# sch.net
KiCad netlist of a schematic drawn in Altium Designer
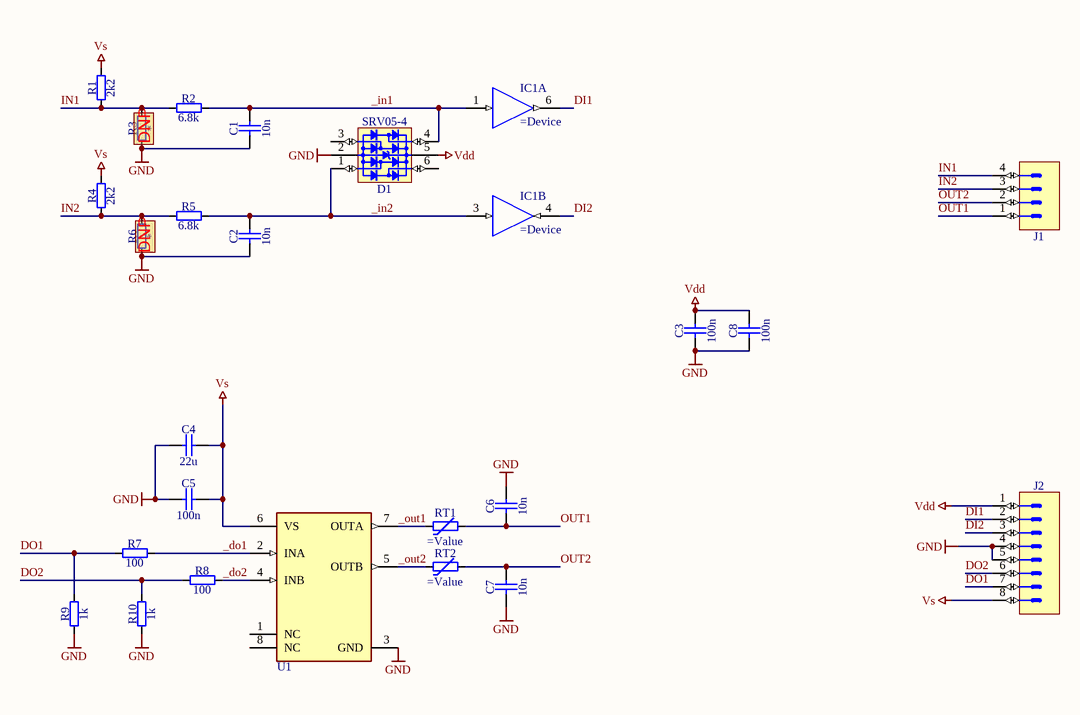
[diagram p0: sch.SchDoc]

(export (version "E")
  (design (tool "Eeschema 10.0.6"))
  (components
    (comp (ref "C1")
      (value "10n")
      (footprint "Capacitors SMD:CAPC1608X85N")
      (description "Non-polarised capacitor")
      (libsource (lib "mopedka ver") (part "Capacitor - non polarized"))
    )
    (comp (ref "C2")
      (value "10n")
      (footprint "Capacitors SMD:CAPC1608X85N")
      (description "Non-polarised capacitor")
      (libsource (lib "mopedka ver") (part "Capacitor - non polarized"))
    )
    (comp (ref "C3")
      (value "100n")
      (footprint "Capacitors SMD:CAPC1608X85N")
      (description "Non-polarised capacitor")
      (libsource (lib "mopedka ver") (part "Capacitor - non polarized"))
    )
    (comp (ref "C4")
      (value "22u")
      (footprint "Capacitors SMD:CAPC3216X140N")
      (description "Non-polarised capacitor")
      (libsource (lib "mopedka ver") (part "Capacitor - non polarized"))
    )
    (comp (ref "C5")
      (value "100n")
      (footprint "Capacitors SMD:CAPC1608X85N")
      (description "Non-polarised capacitor")
      (libsource (lib "mopedka ver") (part "Capacitor - non polarized"))
    )
    (comp (ref "C6")
      (value "10n")
      (footprint "Capacitors SMD:CAPC1608X85N")
      (description "Non-polarised capacitor")
      (libsource (lib "mopedka ver") (part "Capacitor - non polarized"))
    )
    (comp (ref "C7")
      (value "10n")
      (footprint "Capacitors SMD:CAPC1608X85N")
      (description "Non-polarised capacitor")
      (libsource (lib "mopedka ver") (part "Capacitor - non polarized"))
    )
    (comp (ref "C8")
      (value "100n")
      (footprint "Capacitors SMD:CAPC1608X85N")
      (description "Non-polarised capacitor")
      (libsource (lib "mopedka ver") (part "Capacitor - non polarized"))
    )
    (comp (ref "D1")
      (value "SRV05-4")
      (footprint "ICs And Semiconductors SMD:SOT95P280X110-6N")
      (description "RailClamps Low Capacitance TVS Diode Array")
      (libsource (lib "mopedka ver") (part "SRV05-4"))
    )
    (comp (ref "IC1")
      (value "~")
      (footprint "ICs And Semiconductors SMD:SOT65P220X110-6N")
      (description "Dual Schmitt-Trigger Buffer")
      (libsource (lib "mopedka ver") (part "742G17"))
    )
    (comp (ref "J1")
      (value "~")
      (footprint "Connectors THD:MOLEX_22-27-2041")
      (description "Connector 4 Male")
      (libsource (lib "Connectors") (part "Connector 4 Male"))
    )
    (comp (ref "J2")
      (value "~")
      (footprint "MOLEX THD:MOLEX_22-27-2081")
      (description "Connector 8 Male")
      (libsource (lib "Connectors") (part "Connector 8 Male"))
    )
    (comp (ref "R1")
      (value "2k2")
      (footprint "Resistors SMD:RESC3116X65N")
      (description "Resistor")
      (libsource (lib "mopedka ver") (part "Resistor"))
    )
    (comp (ref "R2")
      (value "6.8k")
      (footprint "Resistors SMD:RESC3116X65N")
      (description "Resistor")
      (libsource (lib "mopedka ver") (part "Resistor"))
    )
    (comp (ref "R3")
      (value "*")
      (footprint "Resistors SMD:RESC1608X55N")
      (description "Resistor")
      (libsource (lib "mopedka ver") (part "Resistor"))
    )
    (comp (ref "R4")
      (value "2k2")
      (footprint "Resistors SMD:RESC3116X65N")
      (description "Resistor")
      (libsource (lib "mopedka ver") (part "Resistor"))
    )
    (comp (ref "R5")
      (value "6.8k")
      (footprint "Resistors SMD:RESC3116X65N")
      (description "Resistor")
      (libsource (lib "mopedka ver") (part "Resistor"))
    )
    (comp (ref "R6")
      (value "*")
      (footprint "Resistors SMD:RESC1608X55N")
      (description "Resistor")
      (libsource (lib "mopedka ver") (part "Resistor"))
    )
    (comp (ref "R7")
      (value "100")
      (footprint "Resistors SMD:RESC1608X55N")
      (description "Resistor")
      (libsource (lib "Resistors") (part "Resistor"))
    )
    (comp (ref "R8")
      (value "100")
      (footprint "Resistors SMD:RESC1608X55N")
      (description "Resistor")
      (libsource (lib "Resistors") (part "Resistor"))
    )
    (comp (ref "R9")
      (value "1k")
      (footprint "Resistors SMD:RESC1608X55N")
      (description "Resistor")
      (libsource (lib "Resistors") (part "Resistor"))
    )
    (comp (ref "R10")
      (value "1k")
      (footprint "Resistors SMD:RESC1608X55N")
      (description "Resistor")
      (libsource (lib "Resistors") (part "Resistor"))
    )
    (comp (ref "RT1")
      (value "~")
      (footprint "Fuses:FUSC_LITTELFUSE_466")
      (description "Thermistor NTC (Positive Temperature Coefficient)")
      (libsource (lib "Resistors") (part "Thermistor PTC"))
    )
    (comp (ref "RT2")
      (value "~")
      (footprint "Fuses:FUSC_LITTELFUSE_466")
      (description "Thermistor NTC (Positive Temperature Coefficient)")
      (libsource (lib "Resistors") (part "Thermistor PTC"))
    )
    (comp (ref "U1")
      (value "IR4427STRPBF")
      (footprint "ICs And Semiconductors SMD:SOIC127P600X175-8N")
      (libsource (lib "IC_Infineon_IR4427STRPBF_eec") (part "IR4427STRPBF"))
    )
  )
  (nets
    (net (code "1") (name "/DI1") (class "Default")
      (node (ref "IC1") (pin "6") (pinfunction "OUT_6") (pintype "output"))
      (node (ref "J2") (pin "2") (pinfunction "2_2") (pintype "bidirectional"))
    )
    (net (code "2") (name "/DI2") (class "Default")
      (node (ref "IC1") (pin "4") (pinfunction "OUT_4") (pintype "input"))
      (node (ref "J2") (pin "3") (pinfunction "3_3") (pintype "bidirectional"))
    )
    (net (code "3") (name "/DO1") (class "Default")
      (node (ref "J2") (pin "7") (pinfunction "7_7") (pintype "bidirectional"))
      (node (ref "R7") (pin "1") (pinfunction "1_1") (pintype "passive"))
      (node (ref "R9") (pin "2") (pinfunction "2_2") (pintype "passive"))
    )
    (net (code "4") (name "/DO2") (class "Default")
      (node (ref "J2") (pin "6") (pinfunction "6_6") (pintype "bidirectional"))
      (node (ref "R10") (pin "2") (pinfunction "2_2") (pintype "passive"))
      (node (ref "R8") (pin "1") (pinfunction "1_1") (pintype "passive"))
    )
    (net (code "5") (name "/IN1") (class "Default")
      (node (ref "J1") (pin "4") (pinfunction "4_4") (pintype "bidirectional"))
      (node (ref "R1") (pin "1") (pinfunction "1_1") (pintype "passive"))
      (node (ref "R2") (pin "1") (pinfunction "1_1") (pintype "passive"))
      (node (ref "R3") (pin "2") (pinfunction "2_2") (pintype "passive"))
    )
    (net (code "6") (name "/IN2") (class "Default")
      (node (ref "J1") (pin "3") (pinfunction "3_3") (pintype "bidirectional"))
      (node (ref "R4") (pin "1") (pinfunction "1_1") (pintype "passive"))
      (node (ref "R5") (pin "1") (pinfunction "1_1") (pintype "passive"))
      (node (ref "R6") (pin "2") (pinfunction "2_2") (pintype "passive"))
    )
    (net (code "7") (name "/OUT1") (class "Default")
      (node (ref "C6") (pin "1") (pinfunction "1_1") (pintype "passive"))
      (node (ref "J1") (pin "1") (pinfunction "1_1") (pintype "bidirectional"))
      (node (ref "RT1") (pin "2") (pinfunction "2_2") (pintype "passive"))
    )
    (net (code "8") (name "/OUT2") (class "Default")
      (node (ref "C7") (pin "2") (pinfunction "2_2") (pintype "passive"))
      (node (ref "J1") (pin "2") (pinfunction "2_2") (pintype "bidirectional"))
      (node (ref "RT2") (pin "2") (pinfunction "2_2") (pintype "passive"))
    )
    (net (code "9") (name "/_do1") (class "Default")
      (node (ref "R7") (pin "2") (pinfunction "2_2") (pintype "passive"))
      (node (ref "U1") (pin "2") (pinfunction "INA_2") (pintype "input"))
    )
    (net (code "10") (name "/_do2") (class "Default")
      (node (ref "R8") (pin "2") (pinfunction "2_2") (pintype "passive"))
      (node (ref "U1") (pin "4") (pinfunction "INB_4") (pintype "input"))
    )
    (net (code "11") (name "/_in1") (class "Default")
      (node (ref "C1") (pin "2") (pinfunction "2_2") (pintype "passive"))
      (node (ref "D1") (pin "4") (pinfunction "I/O3_4") (pintype "bidirectional"))
      (node (ref "IC1") (pin "1") (pinfunction "IN_1") (pintype "input"))
      (node (ref "R2") (pin "2") (pinfunction "2_2") (pintype "passive"))
    )
    (net (code "12") (name "/_in2") (class "Default")
      (node (ref "C2") (pin "2") (pinfunction "2_2") (pintype "passive"))
      (node (ref "D1") (pin "1") (pinfunction "I/O1_1") (pintype "bidirectional"))
      (node (ref "IC1") (pin "3") (pinfunction "IN_3") (pintype "input"))
      (node (ref "R5") (pin "2") (pinfunction "2_2") (pintype "passive"))
    )
    (net (code "13") (name "/_out1") (class "Default")
      (node (ref "RT1") (pin "1") (pinfunction "1_1") (pintype "passive"))
      (node (ref "U1") (pin "7") (pinfunction "OUTA_7") (pintype "output"))
    )
    (net (code "14") (name "/_out2") (class "Default")
      (node (ref "RT2") (pin "1") (pinfunction "1_1") (pintype "passive"))
      (node (ref "U1") (pin "5") (pinfunction "OUTB_5") (pintype "output"))
    )
    (net (code "15") (name "GND") (class "Default")
      (node (ref "C1") (pin "1") (pinfunction "1_1") (pintype "passive"))
      (node (ref "C2") (pin "1") (pinfunction "1_1") (pintype "passive"))
      (node (ref "C3") (pin "1") (pinfunction "1_1") (pintype "passive"))
      (node (ref "C4") (pin "1") (pinfunction "1_1") (pintype "passive"))
      (node (ref "C5") (pin "1") (pinfunction "1_1") (pintype "passive"))
      (node (ref "C6") (pin "2") (pinfunction "2_2") (pintype "passive"))
      (node (ref "C7") (pin "1") (pinfunction "1_1") (pintype "passive"))
      (node (ref "C8") (pin "1") (pinfunction "1_1") (pintype "passive"))
      (node (ref "D1") (pin "2") (pinfunction "GND_2") (pintype "power_in"))
      (node (ref "IC1") (pin "2") (pinfunction "GND_2") (pintype "power_in"))
      (node (ref "J2") (pin "4") (pinfunction "4_4") (pintype "bidirectional"))
      (node (ref "J2") (pin "5") (pinfunction "5_5") (pintype "bidirectional"))
      (node (ref "R10") (pin "1") (pinfunction "1_1") (pintype "passive"))
      (node (ref "R3") (pin "1") (pinfunction "1_1") (pintype "passive"))
      (node (ref "R6") (pin "1") (pinfunction "1_1") (pintype "passive"))
      (node (ref "R9") (pin "1") (pinfunction "1_1") (pintype "passive"))
      (node (ref "U1") (pin "3") (pinfunction "GND_3") (pintype "power_in"))
    )
    (net (code "16") (name "Vdd") (class "Default")
      (node (ref "C3") (pin "2") (pinfunction "2_2") (pintype "passive"))
      (node (ref "C8") (pin "2") (pinfunction "2_2") (pintype "passive"))
      (node (ref "D1") (pin "5") (pinfunction "VBUS_5") (pintype "power_in"))
      (node (ref "IC1") (pin "5") (pinfunction "Vdd_5") (pintype "power_in"))
      (node (ref "J2") (pin "1") (pinfunction "1_1") (pintype "bidirectional"))
    )
    (net (code "17") (name "Vs") (class "Default")
      (node (ref "C4") (pin "2") (pinfunction "2_2") (pintype "passive"))
      (node (ref "C5") (pin "2") (pinfunction "2_2") (pintype "passive"))
      (node (ref "J2") (pin "8") (pinfunction "8_8") (pintype "bidirectional"))
      (node (ref "R1") (pin "2") (pinfunction "2_2") (pintype "passive"))
      (node (ref "R4") (pin "2") (pinfunction "2_2") (pintype "passive"))
      (node (ref "U1") (pin "6") (pinfunction "VS_6") (pintype "power_in"))
    )
    (net (code "18") (name "unconnected-(D1-I{slash}O2-Pad3)") (class "Default")
      (node (ref "D1") (pin "3") (pinfunction "I/O2_3") (pintype "bidirectional"))
    )
    (net (code "19") (name "unconnected-(D1-I{slash}O4-Pad6)") (class "Default")
      (node (ref "D1") (pin "6") (pinfunction "I/O4_6") (pintype "bidirectional"))
    )
    (net (code "20") (name "unconnected-(U1-NC-Pad1)") (class "Default")
      (node (ref "U1") (pin "1") (pinfunction "NC_1") (pintype "passive"))
    )
    (net (code "21") (name "unconnected-(U1-NC-Pad8)") (class "Default")
      (node (ref "U1") (pin "8") (pinfunction "NC_8") (pintype "passive"))
    )
  )
)
